# Example_Quick_Start.net
KiCad netlist of a schematic drawn in EasyEDA Pro
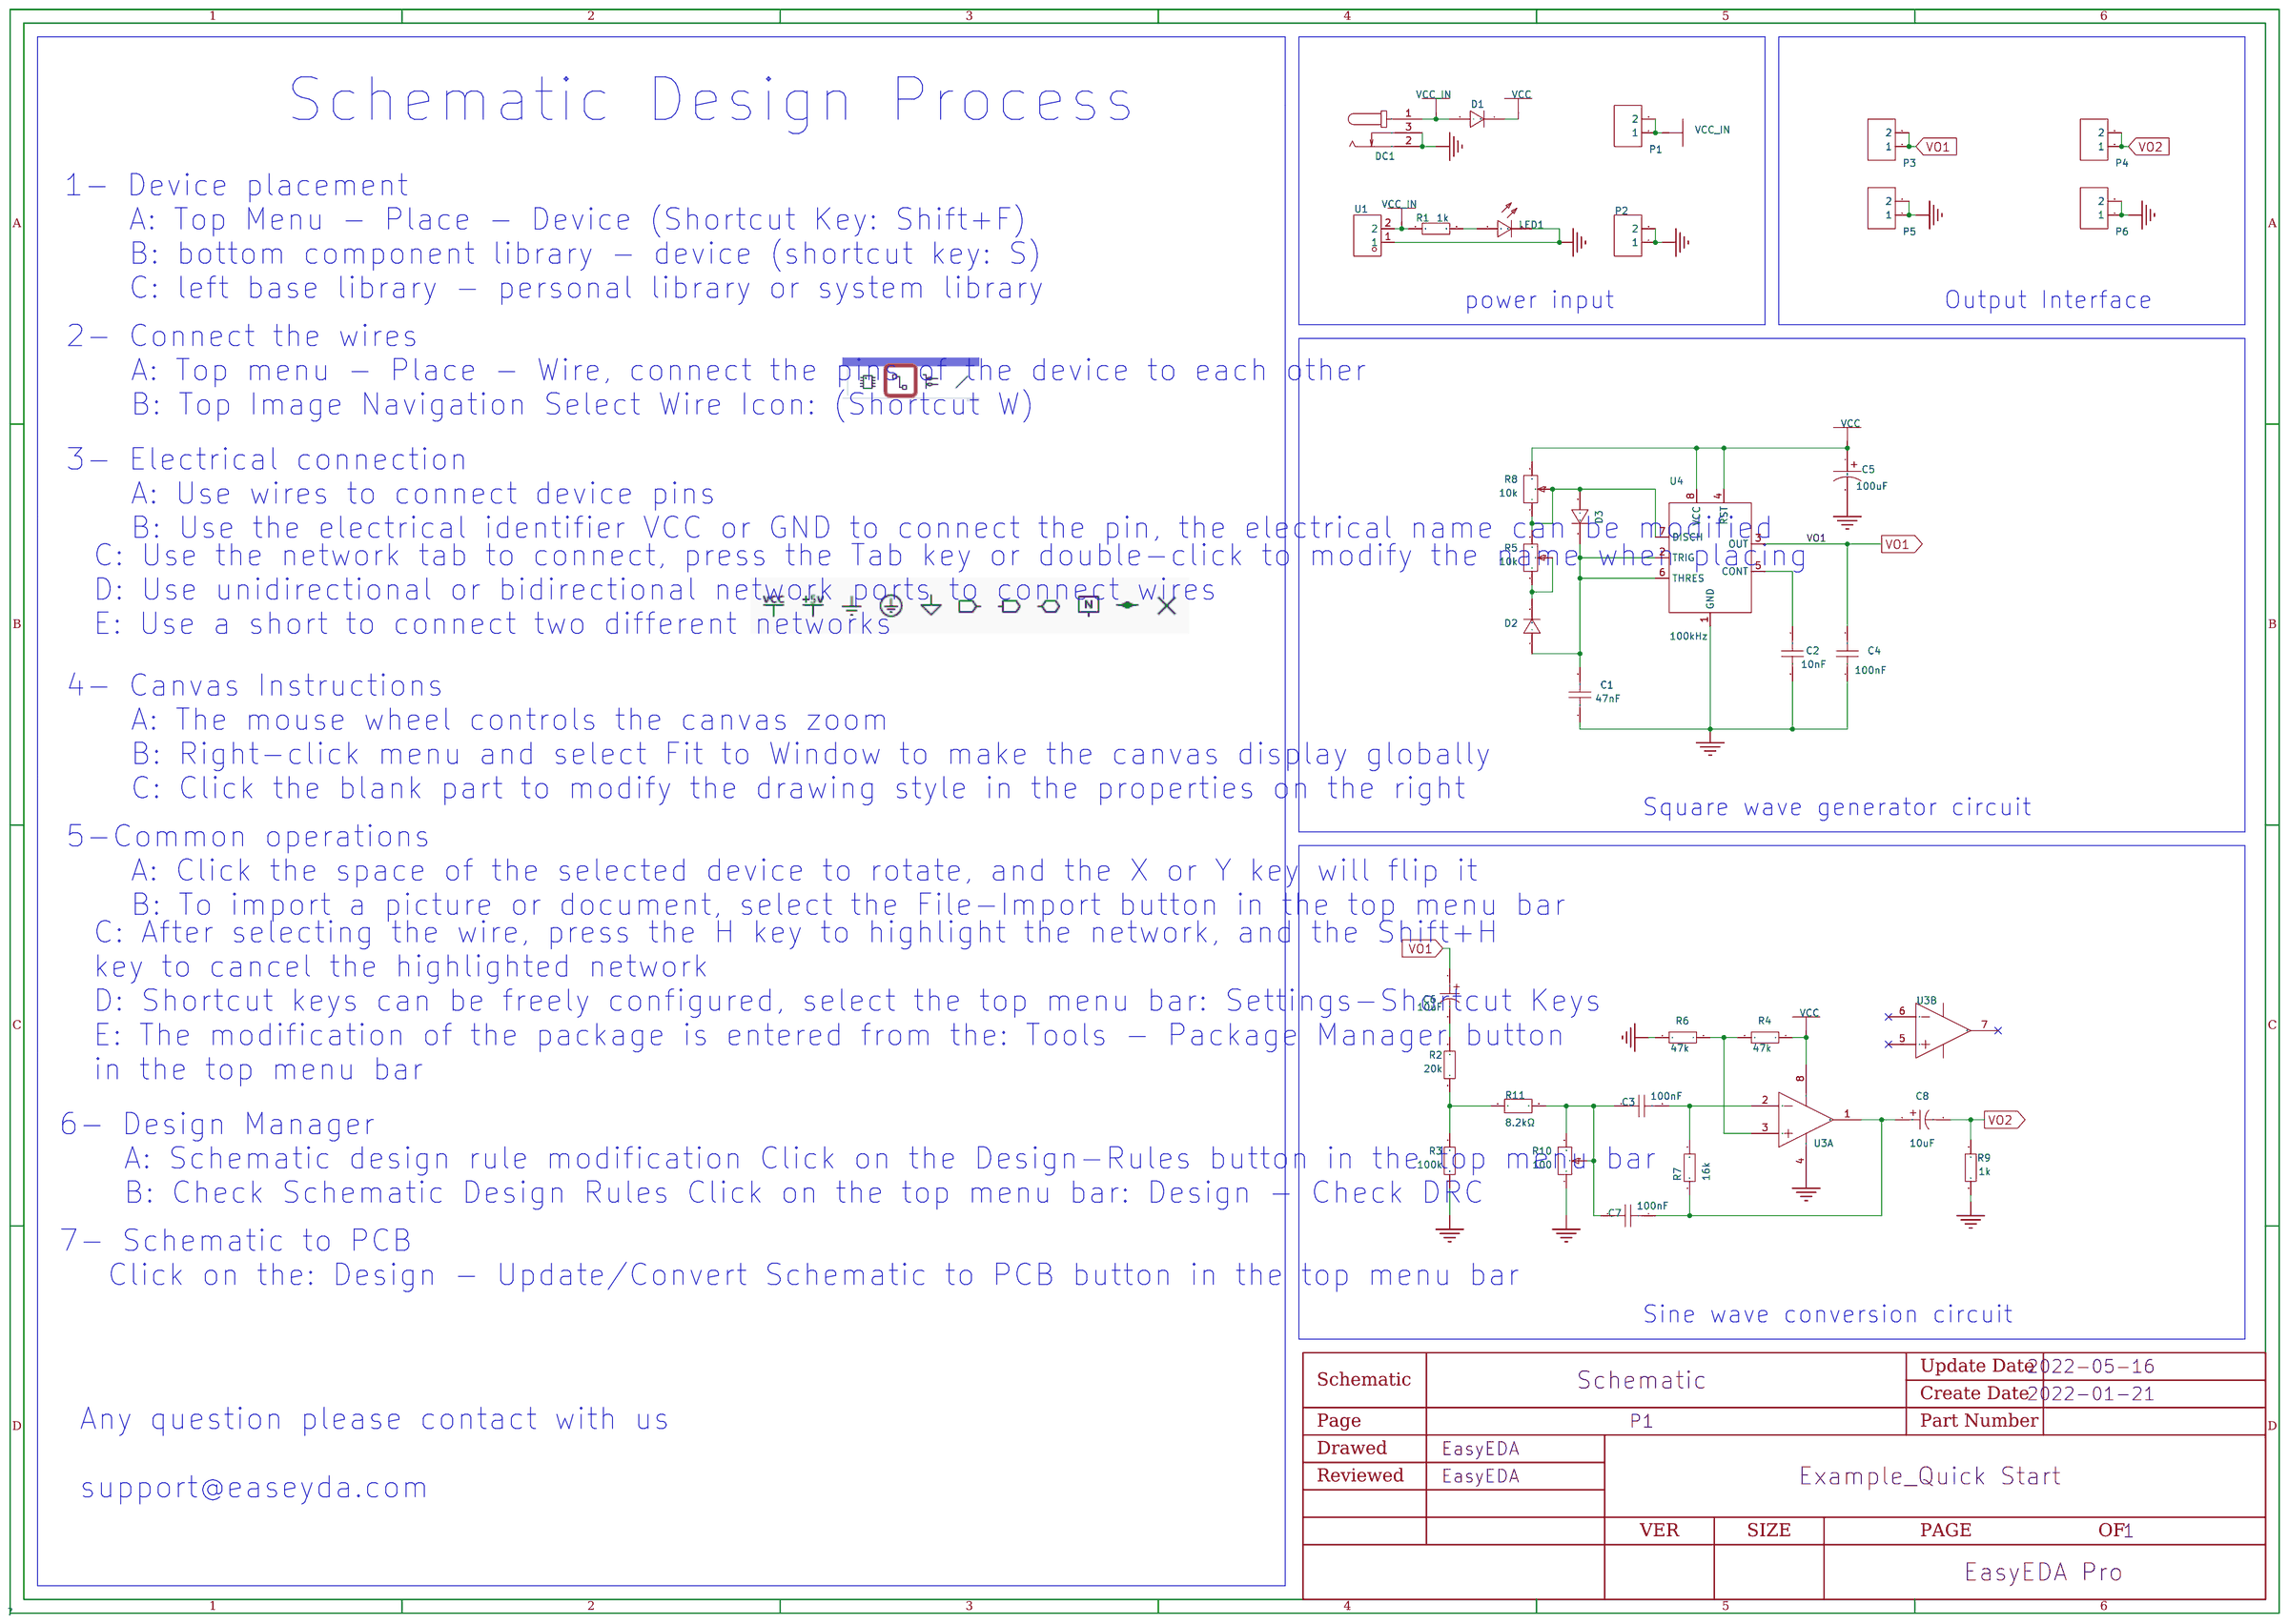
[diagram p0: schematic sheet]

(export (version "E")
  (design (tool "Eeschema 10.0.6"))
  (components
    (comp (ref "C1")
      (value "47nF")
      (footprint "easyedapro:CAP-TH_L3.0-W2.0-P5.08-D0.7")
      (description "容值:47nF;精度:±10%;额定电压:50V;温度系数:X7R;")
      (fields
        (field (name "Manufacturer Part") "CD1H473KC9BER1E000")
        (field (name "Manufacturer") "Dersonic(德尔创)")
      )
      (libsource (lib "easyedapro") (part "CD1H473KC9BER1E000"))
    )
    (comp (ref "C2")
      (value "10nF")
      (footprint "easyedapro:CAP-TH_L5.3-W3.8-P5.08-D0.5")
      (description "容值:10nF;精度:±10%;额定电压:50V;温度系数:X7R;")
      (fields (field (name "Manufacturer Part") "CT4-0805B103K500F1") (field (name "Manufacturer") "FH(风华)"))
      (libsource (lib "easyedapro") (part "CT4-0805B103K500F1"))
    )
    (comp (ref "C3")
      (value "100nF")
      (footprint "easyedapro:CAP-TH_L6.5-W3.0-P5.00-D0.6")
      (description "容值:100nF;精度:±20%;额定电压:50V;温度系数:Y5U;脚间距:5mm;")
      (fields
        (field (name "Manufacturer Part") "DCS104M26Y5UF6FJ5A0")
        (field (name "Manufacturer") "SHM(南方宏明)")
      )
      (libsource (lib "easyedapro") (part "DCS104M26Y5UF6FJ5A0"))
    )
    (comp (ref "C4")
      (value "100nF")
      (footprint "easyedapro:CAP-TH_L6.5-W3.0-P5.00-D0.6")
      (description "容值:100nF;精度:±20%;额定电压:50V;温度系数:Y5U;脚间距:5mm;")
      (fields
        (field (name "Manufacturer Part") "DCS104M26Y5UF6FJ5A0")
        (field (name "Manufacturer") "SHM(南方宏明)")
      )
      (libsource (lib "easyedapro") (part "DCS104M26Y5UF6FJ5A0"))
    )
    (comp (ref "C5")
      (value "100uF")
      (footprint "easyedapro:CAP-TH_BD8.0-P3.50-D0.5-FD")
      (description "容值:100uF;精度:±20%;额定电压:63V;电容体直径:8mm;电容体长度:16mm;脚间距:3.5mm;纹波电流:-;等效串联电阻:-;工作寿命:5000hrs@105;工作温度:-;")
      (fields
        (field (name "Manufacturer Part") "RF063M101LO8*16TA-1A1E")
        (field (name "Manufacturer") "BERYL(绿宝石)")
      )
      (libsource (lib "easyedapro") (part "RF063M101LO8*16TA-1A1E"))
    )
    (comp (ref "C6")
      (value "10uF")
      (footprint "easyedapro:CAP-TH_BD10.0-P5.00-D0.6-FD")
      (fields
        (field (name "Manufacturer Part") "LW100M2501017PV4")
        (field (name "Manufacturer") "UNITED(怡德)")
      )
      (libsource (lib "easyedapro") (part "LW100M2501017PV4_1"))
    )
    (comp (ref "C7")
      (value "100nF")
      (footprint "easyedapro:CAP-TH_L6.5-W3.0-P5.00-D0.6")
      (description "容值:100nF;精度:±20%;额定电压:50V;温度系数:Y5U;脚间距:5mm;")
      (fields
        (field (name "Manufacturer Part") "DCS104M26Y5UF6FJ5A0")
        (field (name "Manufacturer") "SHM(南方宏明)")
      )
      (libsource (lib "easyedapro") (part "DCS104M26Y5UF6FJ5A0"))
    )
    (comp (ref "C8")
      (value "10uF")
      (footprint "easyedapro:CAP-TH_BD10.0-P5.00-D0.6-FD")
      (fields
        (field (name "Manufacturer Part") "LW100M2501017PV4")
        (field (name "Manufacturer") "UNITED(怡德)")
      )
      (libsource (lib "easyedapro") (part "LW100M2501017PV4_1"))
    )
    (comp (ref "D1")
      (value "~")
      (footprint "easyedapro:DO-35_BD2.0-L4.2-P8.20-D0.5-RD")
      (fields (field (name "Manufacturer Part") "1N4148TR") (field (name "Manufacturer") "onsemi(安森美)"))
      (libsource (lib "easyedapro") (part "1N4148TR"))
    )
    (comp (ref "D2")
      (value "~")
      (footprint "easyedapro:DO-35_BD2.0-L4.2-P8.20-D0.5-RD")
      (fields (field (name "Manufacturer Part") "1N4148TR") (field (name "Manufacturer") "onsemi(安森美)"))
      (libsource (lib "easyedapro") (part "1N4148TR"))
    )
    (comp (ref "D3")
      (value "~")
      (footprint "easyedapro:DO-35_BD2.0-L4.2-P8.20-D0.5-RD")
      (fields (field (name "Manufacturer Part") "1N4148TR") (field (name "Manufacturer") "onsemi(安森美)"))
      (libsource (lib "easyedapro") (part "1N4148TR"))
    )
    (comp (ref "DC1")
      (value "~")
      (footprint "easyedapro:DC-IN-TH_DC005-T20")
      (description "触点内径:-;触点外径:-;额定电流:-;额定电压:-;")
      (fields (field (name "Manufacturer Part") "DC005-T20") (field (name "Manufacturer") "SOFNG(硕方)"))
      (libsource (lib "easyedapro") (part "DC005-2.0MM_1"))
    )
    (comp (ref "LED1")
      (value "~")
      (footprint "easyedapro:LED-TH_BD3.8-P2.54-FD")
      (description "发光颜色:红灯;")
      (fields
        (field (name "Manufacturer Part") "204-10SDRD/S530-A3-L")
        (field (name "Manufacturer") "EVERLIGHT(台湾亿光)")
      )
      (libsource (lib "easyedapro") (part "204-10SDRD/S530-A3-L"))
    )
    (comp (ref "P1")
      (value "~")
      (footprint "easyedapro:HDR-TH_2P-P2.54-V-F")
      (description "间距:2.54mm;总孔位数:2;排数:1;插孔结构:1x2P;行距:-;安装类型:直插;塑高:-;触头材质:-;触头镀层:-;")
      (fields (field (name "Manufacturer Part") "2.54-1*2P母") (field (name "Manufacturer") "BOOMELE(博穆精密)"))
      (libsource (lib "easyedapro") (part "Header-Female-2.54_1x2"))
    )
    (comp (ref "P2")
      (value "~")
      (footprint "easyedapro:HDR-TH_2P-P2.54-V-F")
      (description "间距:2.54mm;总孔位数:2;排数:1;插孔结构:1x2P;行距:-;安装类型:直插;塑高:-;触头材质:-;触头镀层:-;")
      (fields (field (name "Manufacturer Part") "2.54-1*2P母") (field (name "Manufacturer") "BOOMELE(博穆精密)"))
      (libsource (lib "easyedapro") (part "Header-Female-2.54_1x2"))
    )
    (comp (ref "P3")
      (value "~")
      (footprint "easyedapro:HDR-TH_2P-P2.54-V-F")
      (description "间距:2.54mm;总孔位数:2;排数:1;插孔结构:1x2P;行距:-;安装类型:直插;塑高:-;触头材质:-;触头镀层:-;")
      (fields (field (name "Manufacturer Part") "2.54-1*2P母") (field (name "Manufacturer") "BOOMELE(博穆精密)"))
      (libsource (lib "easyedapro") (part "Header-Female-2.54_1x2"))
    )
    (comp (ref "P4")
      (value "~")
      (footprint "easyedapro:HDR-TH_2P-P2.54-V-F")
      (description "间距:2.54mm;总孔位数:2;排数:1;插孔结构:1x2P;行距:-;安装类型:直插;塑高:-;触头材质:-;触头镀层:-;")
      (fields (field (name "Manufacturer Part") "2.54-1*2P母") (field (name "Manufacturer") "BOOMELE(博穆精密)"))
      (libsource (lib "easyedapro") (part "Header-Female-2.54_1x2"))
    )
    (comp (ref "P5")
      (value "~")
      (footprint "easyedapro:HDR-TH_2P-P2.54-V-F")
      (description "间距:2.54mm;总孔位数:2;排数:1;插孔结构:1x2P;行距:-;安装类型:直插;塑高:-;触头材质:-;触头镀层:-;")
      (fields (field (name "Manufacturer Part") "2.54-1*2P母") (field (name "Manufacturer") "BOOMELE(博穆精密)"))
      (libsource (lib "easyedapro") (part "Header-Female-2.54_1x2"))
    )
    (comp (ref "P6")
      (value "~")
      (footprint "easyedapro:HDR-TH_2P-P2.54-V-F")
      (description "间距:2.54mm;总孔位数:2;排数:1;插孔结构:1x2P;行距:-;安装类型:直插;塑高:-;触头材质:-;触头镀层:-;")
      (fields (field (name "Manufacturer Part") "2.54-1*2P母") (field (name "Manufacturer") "BOOMELE(博穆精密)"))
      (libsource (lib "easyedapro") (part "Header-Female-2.54_1x2"))
    )
    (comp (ref "R1")
      (value "1k")
      (footprint "easyedapro:RES-TH_BD2.2-L6.5-P10.50-D0.6")
      (description "电阻类型:金属膜电阻;阻值:1k;精度:±5%;功率:250mW;工作温度范围:-;")
      (fields (field (name "Manufacturer Part") "MFR-25JT-52-1K") (field (name "Manufacturer") "YAGEO(国巨)"))
      (libsource (lib "easyedapro") (part "MFR-25JT-52-1K"))
    )
    (comp (ref "R2")
      (value "20k")
      (footprint "easyedapro:RES-TH_BD2.2-L6.5-P10.50-D0.6")
      (description "电阻类型:金属膜电阻;阻值:20k;精度:±1%;功率:250mW;温度系数:±50ppm/;工作温度范围:-;")
      (fields
        (field (name "Manufacturer Part") "MFR0W4F2002A50")
        (field (name "Manufacturer") "UNI-ROYAL(厚声)")
      )
      (libsource (lib "easyedapro") (part "MFR0W4F2002A50"))
    )
    (comp (ref "R3")
      (value "100k")
      (footprint "easyedapro:RES-TH_BD2.5-L6.5-P10.50-D0.6")
      (description "电阻类型:金属膜电阻;阻值:100k;精度:±1%;功率:250mW;温度系数:±50ppm/;工作温度范围:-;")
      (fields
        (field (name "Manufacturer Part") "MFR0W4F1003A50")
        (field (name "Manufacturer") "UNI-ROYAL(厚声)")
      )
      (libsource (lib "easyedapro") (part "MFR0W4F1003A50"))
    )
    (comp (ref "R4")
      (value "47k")
      (footprint "easyedapro:RES-TH_BD2.4-L6.3-P10.30-D0.6")
      (description "电阻类型:金属膜电阻;阻值:47k;精度:±1%;功率:250mW;温度系数:±50ppm/;工作温度范围:-;")
      (fields (field (name "Manufacturer Part") "MFR-25FTE52-47K") (field (name "Manufacturer") "YAGEO(国巨)"))
      (libsource (lib "easyedapro") (part "MFR-25FTE52-47K"))
    )
    (comp (ref "R5")
      (value "10k")
      (footprint "easyedapro:RES-ADJ-TH_3296W")
      (description "阻值:10k;精度:±10%;温度系数:±250ppm/;")
      (fields (field (name "Manufacturer Part") "3296W-1-103") (field (name "Manufacturer") "BOCHEN(博晨)"))
      (libsource (lib "easyedapro") (part "3296W-1-103_C330432"))
    )
    (comp (ref "R6")
      (value "47k")
      (footprint "easyedapro:RES-TH_BD2.4-L6.3-P10.30-D0.6")
      (description "电阻类型:金属膜电阻;阻值:47k;精度:±1%;功率:250mW;温度系数:±50ppm/;工作温度范围:-;")
      (fields (field (name "Manufacturer Part") "MFR-25FTE52-47K") (field (name "Manufacturer") "YAGEO(国巨)"))
      (libsource (lib "easyedapro") (part "MFR-25FTE52-47K"))
    )
    (comp (ref "R7")
      (value "16k")
      (footprint "easyedapro:RES-TH_BD2.4-L6.3-P10.30-D0.6")
      (description "电阻类型:金属膜电阻;阻值:16k;精度:±1%;功率:250mW;温度系数:±350ppm/;最大工作电压:250V;工作温度范围:-55~+155;")
      (fields (field (name "Manufacturer Part") "MF1/4W ±1% 16K STB5") (field (name "Manufacturer") "VO(翔胜)"))
      (libsource (lib "easyedapro") (part "MF1/4W ±1% 16K STB5"))
    )
    (comp (ref "R8")
      (value "10k")
      (footprint "easyedapro:RES-ADJ-TH_3296W")
      (description "阻值:10k;精度:±10%;温度系数:±250ppm/;")
      (fields (field (name "Manufacturer Part") "3296W-1-103") (field (name "Manufacturer") "BOCHEN(博晨)"))
      (libsource (lib "easyedapro") (part "3296W-1-103_C330432"))
    )
    (comp (ref "R9")
      (value "1k")
      (footprint "easyedapro:RES-TH_BD2.2-L6.5-P10.50-D0.6")
      (description "电阻类型:金属膜电阻;阻值:1k;精度:±5%;功率:250mW;工作温度范围:-;")
      (fields (field (name "Manufacturer Part") "MFR-25JT-52-1K") (field (name "Manufacturer") "YAGEO(国巨)"))
      (libsource (lib "easyedapro") (part "MFR-25JT-52-1K"))
    )
    (comp (ref "R10")
      (value "100")
      (footprint "easyedapro:RES-ADJ-TH_3296W")
      (description "阻值:100;精度:±10%;温度系数:±100ppm/;")
      (fields (field (name "Manufacturer Part") "3296W-1-101LF") (field (name "Manufacturer") "BOURNS"))
      (libsource (lib "easyedapro") (part "3296W-1-101LF"))
    )
    (comp (ref "R11")
      (value "8.2kΩ")
      (footprint "easyedapro:RES-TH_BD2.3-L6.5-P10.50-D0.5")
      (description "电阻类型:金属膜电阻;阻值:8.2kΩ;精度:±1%;功率:250mW;温度系数:±200ppm/°C;工作温度范围:-;")
      (fields (field (name "Manufacturer Part") "MF1/4W-8.2KΩ±1%T52") (field (name "Manufacturer") "华星机电"))
      (libsource (lib "easyedapro") (part "MF1/4W-8.2KΩ±1%T52"))
    )
    (comp (ref "U1")
      (value "~")
      (footprint "easyedapro:CONN-TH_2P-P5.00_DB301V-5.0-2P-BU-P")
      (fields
        (field (name "Manufacturer Part") "DB301V-5.0-2P-BU-P")
        (field (name "Manufacturer") "DIBO(地博电气)")
      )
      (libsource (lib "easyedapro") (part "DB301V-5.0-2P-BU-P"))
    )
    (comp (ref "U3")
      (value "~")
      (footprint "easyedapro:DIP-8_L9.6-W6.4-P2.54-LS7.6-BL-1")
      (description "运放类型:J-FET;放大器组数:2;增益带宽积（GBP）:3MHz;压摆率（SR）:13 V/us;电源电压:7V~36V,±3.5V~18V;各通道供电电流:1.4mA;")
      (fields (field (name "Manufacturer Part") "TL072CP") (field (name "Manufacturer") "TI(德州仪器)"))
      (libsource (lib "easyedapro") (part "TL072CP"))
    )
    (comp (ref "U4")
      (value "100kHz")
      (footprint "easyedapro:SOIC-8_L4.9-W3.9-P1.27-LS6.0-BL")
      (description "类型:555 型，计时器/振荡器(单路);计数:-;频率:100kHz;工作电压:4.5V~16V;工作电流:10mA;工作温度:0~+70;")
      (fields (field (name "Manufacturer Part") "NE555DR") (field (name "Manufacturer") "TI(德州仪器)"))
      (libsource (lib "easyedapro") (part "NE555DR"))
    )
  )
  (nets
    (net (code "1") (name "GND") (class "Default")
      (node (ref "C1") (pin "1") (pinfunction "1_1") (pintype "input"))
      (node (ref "C2") (pin "2") (pinfunction "2_2") (pintype "input"))
      (node (ref "C4") (pin "1") (pinfunction "1_1") (pintype "input"))
      (node (ref "C5") (pin "2") (pinfunction "2_2") (pintype "input"))
      (node (ref "DC1") (pin "2") (pinfunction "2_2") (pintype "input"))
      (node (ref "DC1") (pin "3") (pinfunction "3_3") (pintype "input"))
      (node (ref "LED1") (pin "2") (pinfunction "C_2") (pintype "input"))
      (node (ref "P2") (pin "1") (pinfunction "1_1") (pintype "input"))
      (node (ref "P2") (pin "2") (pinfunction "2_2") (pintype "input"))
      (node (ref "P5") (pin "1") (pinfunction "1_1") (pintype "input"))
      (node (ref "P5") (pin "2") (pinfunction "2_2") (pintype "input"))
      (node (ref "P6") (pin "1") (pinfunction "1_1") (pintype "input"))
      (node (ref "P6") (pin "2") (pinfunction "2_2") (pintype "input"))
      (node (ref "R10") (pin "1") (pinfunction "1_1") (pintype "input"))
      (node (ref "R3") (pin "1") (pinfunction "1_1") (pintype "input"))
      (node (ref "R6") (pin "2") (pinfunction "2_2") (pintype "input"))
      (node (ref "R9") (pin "1") (pinfunction "1_1") (pintype "input"))
      (node (ref "U1") (pin "1") (pinfunction "1_1") (pintype "input"))
      (node (ref "U3") (pin "4") (pinfunction "VCC-_4") (pintype "input"))
      (node (ref "U4") (pin "1") (pinfunction "GND_1") (pintype "input"))
    )
    (net (code "2") (name "Net-(C3-Pad2)") (class "Default")
      (node (ref "C3") (pin "2") (pinfunction "2_2") (pintype "input"))
      (node (ref "C7") (pin "2") (pinfunction "2_2") (pintype "input"))
      (node (ref "R10") (pin "2") (pinfunction "2_2") (pintype "input"))
      (node (ref "R10") (pin "3") (pinfunction "3_3") (pintype "input"))
      (node (ref "R11") (pin "2") (pinfunction "2_2") (pintype "input"))
    )
    (net (code "3") (name "Net-(C6-Pad2)") (class "Default")
      (node (ref "C6") (pin "2") (pinfunction "2_2") (pintype "input"))
      (node (ref "R2") (pin "2") (pinfunction "2_2") (pintype "input"))
    )
    (net (code "4") (name "Net-(D2-A)") (class "Default")
      (node (ref "C1") (pin "2") (pinfunction "2_2") (pintype "input"))
      (node (ref "D2") (pin "2") (pinfunction "A_2") (pintype "input"))
      (node (ref "D3") (pin "1") (pinfunction "C_1") (pintype "input"))
      (node (ref "U4") (pin "2") (pinfunction "TRIG_2") (pintype "input"))
      (node (ref "U4") (pin "6") (pinfunction "THRES_6") (pintype "input"))
    )
    (net (code "5") (name "Net-(D2-C)") (class "Default")
      (node (ref "D2") (pin "1") (pinfunction "C_1") (pintype "input"))
      (node (ref "R5") (pin "1") (pinfunction "1_1") (pintype "input"))
      (node (ref "R5") (pin "2") (pinfunction "2_2") (pintype "input"))
    )
    (net (code "6") (name "Net-(D3-A)") (class "Default")
      (node (ref "D3") (pin "2") (pinfunction "A_2") (pintype "input"))
      (node (ref "R5") (pin "3") (pinfunction "3_3") (pintype "input"))
      (node (ref "R8") (pin "1") (pinfunction "1_1") (pintype "input"))
      (node (ref "R8") (pin "2") (pinfunction "2_2") (pintype "input"))
      (node (ref "U4") (pin "7") (pinfunction "DISCH_7") (pintype "input"))
    )
    (net (code "7") (name "Net-(LED1-A)") (class "Default")
      (node (ref "LED1") (pin "1") (pinfunction "A_1") (pintype "input"))
      (node (ref "R1") (pin "2") (pinfunction "2_2") (pintype "input"))
    )
    (net (code "8") (name "Net-(R11-Pad1)") (class "Default")
      (node (ref "R11") (pin "1") (pinfunction "1_1") (pintype "input"))
      (node (ref "R2") (pin "1") (pinfunction "1_1") (pintype "input"))
      (node (ref "R3") (pin "2") (pinfunction "2_2") (pintype "input"))
    )
    (net (code "9") (name "Net-(U3A-IN1+)") (class "Default")
      (node (ref "R4") (pin "2") (pinfunction "2_2") (pintype "input"))
      (node (ref "R6") (pin "1") (pinfunction "1_1") (pintype "input"))
      (node (ref "U3") (pin "3") (pinfunction "IN1+_3") (pintype "input"))
    )
    (net (code "10") (name "Net-(U3A-IN1-)") (class "Default")
      (node (ref "C3") (pin "1") (pinfunction "1_1") (pintype "input"))
      (node (ref "R7") (pin "2") (pinfunction "2_2") (pintype "input"))
      (node (ref "U3") (pin "2") (pinfunction "IN1-_2") (pintype "input"))
    )
    (net (code "11") (name "Net-(U3A-OUT1)") (class "Default")
      (node (ref "C7") (pin "1") (pinfunction "1_1") (pintype "input"))
      (node (ref "C8") (pin "1") (pinfunction "1_1") (pintype "input"))
      (node (ref "R7") (pin "1") (pinfunction "1_1") (pintype "input"))
      (node (ref "U3") (pin "1") (pinfunction "OUT1_1") (pintype "output"))
    )
    (net (code "12") (name "Net-(U4-CONT)") (class "Default")
      (node (ref "C2") (pin "1") (pinfunction "1_1") (pintype "input"))
      (node (ref "U4") (pin "5") (pinfunction "CONT_5") (pintype "input"))
    )
    (net (code "13") (name "VCC") (class "Default")
      (node (ref "C5") (pin "1") (pinfunction "1_1") (pintype "input"))
      (node (ref "D1") (pin "1") (pinfunction "C_1") (pintype "input"))
      (node (ref "R4") (pin "1") (pinfunction "1_1") (pintype "input"))
      (node (ref "R8") (pin "3") (pinfunction "3_3") (pintype "input"))
      (node (ref "U3") (pin "8") (pinfunction "VCC+_8") (pintype "input"))
      (node (ref "U4") (pin "4") (pinfunction "RST_4") (pintype "input"))
      (node (ref "U4") (pin "8") (pinfunction "VCC_8") (pintype "input"))
    )
    (net (code "14") (name "VCC_IN") (class "Default")
      (node (ref "D1") (pin "2") (pinfunction "A_2") (pintype "input"))
      (node (ref "DC1") (pin "1") (pinfunction "1_1") (pintype "input"))
      (node (ref "P1") (pin "1") (pinfunction "1_1") (pintype "input"))
      (node (ref "P1") (pin "2") (pinfunction "2_2") (pintype "input"))
      (node (ref "R1") (pin "1") (pinfunction "1_1") (pintype "input"))
      (node (ref "U1") (pin "2") (pinfunction "2_2") (pintype "input"))
    )
    (net (code "15") (name "VO1") (class "Default")
      (node (ref "C4") (pin "2") (pinfunction "2_2") (pintype "input"))
      (node (ref "C6") (pin "1") (pinfunction "1_1") (pintype "input"))
      (node (ref "P3") (pin "1") (pinfunction "1_1") (pintype "input"))
      (node (ref "P3") (pin "2") (pinfunction "2_2") (pintype "input"))
      (node (ref "U4") (pin "3") (pinfunction "OUT_3") (pintype "input"))
    )
    (net (code "16") (name "VO2") (class "Default")
      (node (ref "C8") (pin "2") (pinfunction "2_2") (pintype "input"))
      (node (ref "P4") (pin "1") (pinfunction "1_1") (pintype "input"))
      (node (ref "P4") (pin "2") (pinfunction "2_2") (pintype "input"))
      (node (ref "R9") (pin "2") (pinfunction "2_2") (pintype "input"))
    )
    (net (code "17") (name "unconnected-(U3B-IN2+-Pad5)") (class "Default")
      (node (ref "U3") (pin "5") (pinfunction "IN2+_5") (pintype "input+no_connect"))
    )
    (net (code "18") (name "unconnected-(U3B-IN2--Pad6)") (class "Default")
      (node (ref "U3") (pin "6") (pinfunction "IN2-_6") (pintype "input+no_connect"))
    )
    (net (code "19") (name "unconnected-(U3B-OUT2-Pad7)") (class "Default")
      (node (ref "U3") (pin "7") (pinfunction "OUT2_7") (pintype "output+no_connect"))
    )
  )
)
